# Power.net
KiCad netlist of a schematic drawn in Altium Designer
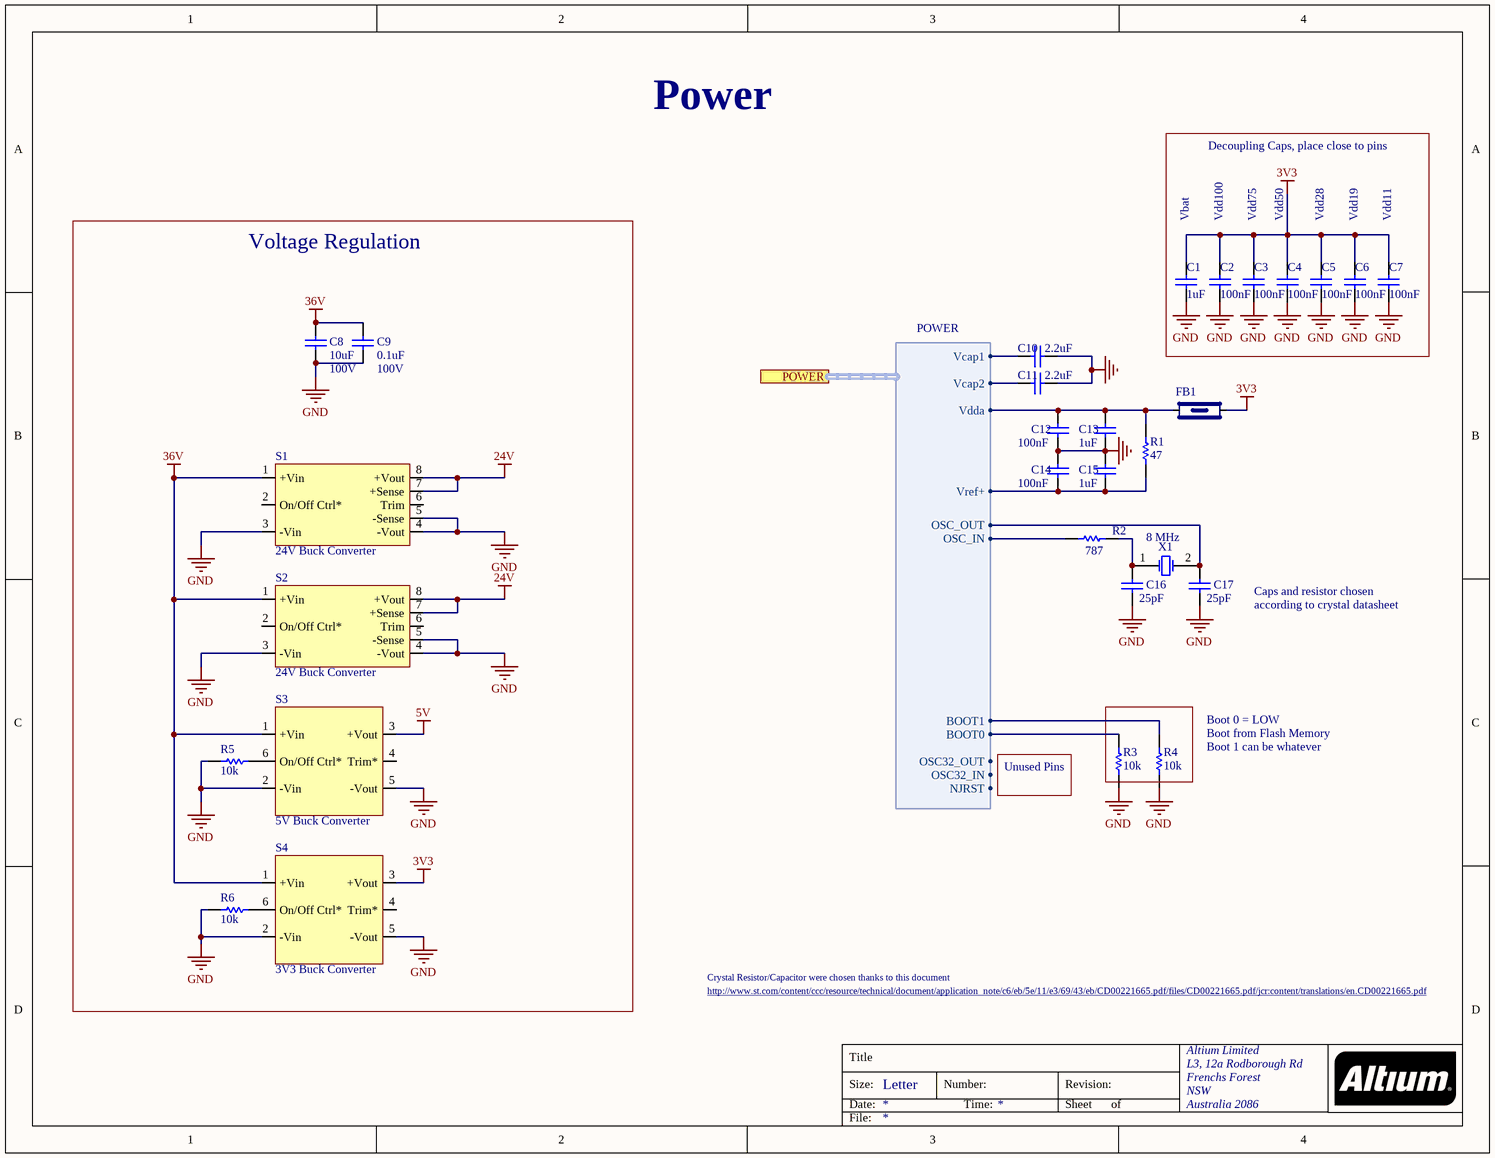
[diagram p0: Power.SchDoc]

(export (version "E")
  (design (tool "Eeschema 10.0.6"))
  (components
    (comp (ref "C1")
      (value "1uF")
      (footprint "CAP_0603")
      (description "Capacitor")
      (libsource (lib "Miscellaneous Devices") (part "Cap"))
    )
    (comp (ref "C2")
      (value "100nF")
      (footprint "CAP_0603")
      (description "Capacitor")
      (libsource (lib "Miscellaneous Devices") (part "Cap"))
    )
    (comp (ref "C3")
      (value "100nF")
      (footprint "CAP_0603")
      (description "Capacitor")
      (libsource (lib "Miscellaneous Devices") (part "Cap"))
    )
    (comp (ref "C4")
      (value "100nF")
      (footprint "CAP_0603")
      (description "Capacitor")
      (libsource (lib "Miscellaneous Devices") (part "Cap"))
    )
    (comp (ref "C5")
      (value "100nF")
      (footprint "CAP_0603")
      (description "Capacitor")
      (libsource (lib "Miscellaneous Devices") (part "Cap"))
    )
    (comp (ref "C6")
      (value "100nF")
      (footprint "CAP_0603")
      (description "Capacitor")
      (libsource (lib "Miscellaneous Devices") (part "Cap"))
    )
    (comp (ref "C7")
      (value "100nF")
      (footprint "CAP_0603")
      (description "Capacitor")
      (libsource (lib "Miscellaneous Devices") (part "Cap"))
    )
    (comp (ref "C8")
      (value "10uF")
      (footprint "2220")
      (description "Capacitor")
      (fields
        (field (name "VOLTAGE") "100V")
        (field (name "Comment") "Cap")
        (field (name "PUBLISHER") "Altium Limited")
      )
      (libsource (lib "Miscellaneous Devices") (part "Cap"))
    )
    (comp (ref "C9")
      (value "0.1uF")
      (footprint "CAP_0603")
      (description "Capacitor")
      (fields
        (field (name "VOLTAGE") "100V")
        (field (name "Comment") "Cap")
        (field (name "PUBLISHER") "Altium Limited")
      )
      (libsource (lib "Miscellaneous Devices") (part "Cap"))
    )
    (comp (ref "C10")
      (value "2.2uF")
      (footprint "CAP_0603")
      (description "Capacitor")
      (libsource (lib "Miscellaneous Devices") (part "Cap"))
    )
    (comp (ref "C11")
      (value "2.2uF")
      (footprint "CAP_0603")
      (description "Capacitor")
      (libsource (lib "Miscellaneous Devices") (part "Cap"))
    )
    (comp (ref "C12")
      (value "100nF")
      (footprint "CAP_0603")
      (description "Capacitor")
      (libsource (lib "Miscellaneous Devices") (part "Cap"))
    )
    (comp (ref "C13")
      (value "1uF")
      (footprint "CAP_0603")
      (description "Capacitor")
      (libsource (lib "Miscellaneous Devices") (part "Cap"))
    )
    (comp (ref "C14")
      (value "100nF")
      (footprint "CAP_0603")
      (description "Capacitor")
      (libsource (lib "Miscellaneous Devices") (part "Cap"))
    )
    (comp (ref "C15")
      (value "1uF")
      (footprint "CAP_0603")
      (description "Capacitor")
      (libsource (lib "Miscellaneous Devices") (part "Cap"))
    )
    (comp (ref "C16")
      (value "25pF")
      (footprint "CAP_0603")
      (description "Capacitor")
      (libsource (lib "Miscellaneous Devices") (part "Cap"))
    )
    (comp (ref "C17")
      (value "25pF")
      (footprint "CAP_0603")
      (description "Capacitor")
      (libsource (lib "Miscellaneous Devices") (part "Cap"))
    )
    (comp (ref "FB1")
      (value "Ferrite Bead")
      (footprint "0603")
      (libsource (lib "LaunchyRIOComponents") (part "Ferrite Bead"))
    )
    (comp (ref "R1")
      (value "47")
      (footprint "RES_0603")
      (description "Resistor")
      (fields (field (name "Comment") "Res1"))
      (libsource (lib "Miscellaneous Devices") (part "Res1"))
    )
    (comp (ref "R2")
      (value "787")
      (footprint "RES_0603")
      (description "Resistor")
      (fields (field (name "Comment") "Res1"))
      (libsource (lib "Miscellaneous Devices") (part "Res1"))
    )
    (comp (ref "R3")
      (value "10k")
      (footprint "RES_0603")
      (description "Resistor")
      (fields (field (name "Comment") "Res1"))
      (libsource (lib "Miscellaneous Devices") (part "Res1"))
    )
    (comp (ref "R4")
      (value "10k")
      (footprint "RES_0603")
      (description "Resistor")
      (fields (field (name "Comment") "Res1"))
      (libsource (lib "Miscellaneous Devices") (part "Res1"))
    )
    (comp (ref "R5")
      (value "10k")
      (footprint "RES_0603")
      (description "Resistor")
      (fields (field (name "Comment") "Res1"))
      (libsource (lib "Miscellaneous Devices") (part "Res1"))
    )
    (comp (ref "R6")
      (value "10k")
      (footprint "RES_0603")
      (description "Resistor")
      (fields (field (name "Comment") "Res1"))
      (libsource (lib "Miscellaneous Devices") (part "Res1"))
    )
    (comp (ref "S1")
      (value "24V Buck Converter")
      (footprint "UWE-24/3-Q12")
      (description "CONV DC/DC 72W 24V 3A")
      (libsource (lib "LaunchyRIOComponents") (part "UWE-24/3-Q12PB-C"))
    )
    (comp (ref "S2")
      (value "24V Buck Converter")
      (footprint "UWE-24/3-Q12")
      (description "CONV DC/DC 72W 24V 3A")
      (libsource (lib "LaunchyRIOComponents") (part "UWE-24/3-Q12PB-C"))
    )
    (comp (ref "S3")
      (value "5V Buck Converter")
      (footprint "SPM15-050-Q12P-C")
      (description "DC/DC CONVERTER 5V 15W")
      (libsource (lib "LaunchyRIOComponents") (part "SPM15-050-Q12P-C"))
    )
    (comp (ref "S4")
      (value "3V3 Buck Converter")
      (footprint "SPM15-033-Q48N-C")
      (description "DC/DC CONVERTER 3.3V 15W")
      (libsource (lib "LaunchyRIOComponents") (part "SPM15-033-Q12P-C"))
    )
    (comp (ref "X1")
      (value "XTAL")
      (footprint "OSC_8MHz")
      (description "Crystal Oscillator")
      (fields (field (name "FREQUENCY") "8 MHz"))
      (libsource (lib "Miscellaneous Devices") (part "XTAL"))
    )
  )
  (nets
    (net (code "2") (name "/BOOT0") (class "Default")
      (node (ref "R3") (pin "2") (pinfunction "2_2") (pintype "passive"))
    )
    (net (code "3") (name "/BOOT1") (class "Default")
      (node (ref "R4") (pin "2") (pinfunction "2_2") (pintype "passive"))
    )
    (net (code "4") (name "/OSC_IN") (class "Default")
      (node (ref "R2") (pin "2") (pinfunction "2_2") (pintype "passive"))
    )
    (net (code "5") (name "/OSC_OUT") (class "Default")
      (node (ref "C17") (pin "2") (pinfunction "2_2") (pintype "passive"))
      (node (ref "X1") (pin "2") (pinfunction "OSC2_2") (pintype "passive"))
    )
    (net (code "6") (name "/Vcap1") (class "Default")
      (node (ref "C10") (pin "2") (pinfunction "2_2") (pintype "passive"))
    )
    (net (code "7") (name "/Vcap2") (class "Default")
      (node (ref "C11") (pin "2") (pinfunction "2_2") (pintype "passive"))
    )
    (net (code "8") (name "/Vdda") (class "Default")
      (node (ref "C12") (pin "2") (pinfunction "2_2") (pintype "passive"))
      (node (ref "C13") (pin "2") (pinfunction "2_2") (pintype "passive"))
      (node (ref "FB1") (pin "1") (pinfunction "1_1") (pintype "passive"))
      (node (ref "R1") (pin "2") (pinfunction "2_2") (pintype "passive"))
    )
    (net (code "9") (name "/Vref+") (class "Default")
      (node (ref "C14") (pin "1") (pinfunction "1_1") (pintype "passive"))
      (node (ref "C15") (pin "1") (pinfunction "1_1") (pintype "passive"))
      (node (ref "R1") (pin "1") (pinfunction "1_1") (pintype "passive"))
    )
    (net (code "11") (name "3V3") (class "Default")
      (node (ref "C1") (pin "2") (pinfunction "2_2") (pintype "passive"))
      (node (ref "C2") (pin "2") (pinfunction "2_2") (pintype "passive"))
      (node (ref "C3") (pin "2") (pinfunction "2_2") (pintype "passive"))
      (node (ref "C4") (pin "2") (pinfunction "2_2") (pintype "passive"))
      (node (ref "C5") (pin "2") (pinfunction "2_2") (pintype "passive"))
      (node (ref "C6") (pin "2") (pinfunction "2_2") (pintype "passive"))
      (node (ref "C7") (pin "2") (pinfunction "2_2") (pintype "passive"))
      (node (ref "FB1") (pin "2") (pinfunction "2_2") (pintype "passive"))
      (node (ref "S4") (pin "3") (pinfunction "+Vout_3") (pintype "passive"))
    )
    (net (code "12") (name "5V") (class "Default")
      (node (ref "S3") (pin "3") (pinfunction "+Vout_3") (pintype "passive"))
    )
    (net (code "13") (name "24V") (class "Default")
      (node (ref "S1") (pin "7") (pinfunction "+Sense_7") (pintype "passive"))
      (node (ref "S1") (pin "8") (pinfunction "+Vout_8") (pintype "passive"))
      (node (ref "S2") (pin "7") (pinfunction "+Sense_7") (pintype "passive"))
      (node (ref "S2") (pin "8") (pinfunction "+Vout_8") (pintype "passive"))
    )
    (net (code "14") (name "36V") (class "Default")
      (node (ref "C8") (pin "2") (pinfunction "2_2") (pintype "passive"))
      (node (ref "C9") (pin "2") (pinfunction "2_2") (pintype "passive"))
      (node (ref "S1") (pin "1") (pinfunction "+Vin_1") (pintype "passive"))
      (node (ref "S2") (pin "1") (pinfunction "+Vin_1") (pintype "passive"))
      (node (ref "S3") (pin "1") (pinfunction "+Vin_1") (pintype "passive"))
      (node (ref "S4") (pin "1") (pinfunction "+Vin_1") (pintype "passive"))
    )
    (net (code "15") (name "GND") (class "Default")
      (node (ref "C1") (pin "1") (pinfunction "1_1") (pintype "passive"))
      (node (ref "C10") (pin "1") (pinfunction "1_1") (pintype "passive"))
      (node (ref "C11") (pin "1") (pinfunction "1_1") (pintype "passive"))
      (node (ref "C12") (pin "1") (pinfunction "1_1") (pintype "passive"))
      (node (ref "C13") (pin "1") (pinfunction "1_1") (pintype "passive"))
      (node (ref "C14") (pin "2") (pinfunction "2_2") (pintype "passive"))
      (node (ref "C15") (pin "2") (pinfunction "2_2") (pintype "passive"))
      (node (ref "C16") (pin "1") (pinfunction "1_1") (pintype "passive"))
      (node (ref "C17") (pin "1") (pinfunction "1_1") (pintype "passive"))
      (node (ref "C2") (pin "1") (pinfunction "1_1") (pintype "passive"))
      (node (ref "C3") (pin "1") (pinfunction "1_1") (pintype "passive"))
      (node (ref "C4") (pin "1") (pinfunction "1_1") (pintype "passive"))
      (node (ref "C5") (pin "1") (pinfunction "1_1") (pintype "passive"))
      (node (ref "C6") (pin "1") (pinfunction "1_1") (pintype "passive"))
      (node (ref "C7") (pin "1") (pinfunction "1_1") (pintype "passive"))
      (node (ref "C8") (pin "1") (pinfunction "1_1") (pintype "passive"))
      (node (ref "C9") (pin "1") (pinfunction "1_1") (pintype "passive"))
      (node (ref "R3") (pin "1") (pinfunction "1_1") (pintype "passive"))
      (node (ref "R4") (pin "1") (pinfunction "1_1") (pintype "passive"))
      (node (ref "R5") (pin "2") (pinfunction "2_2") (pintype "passive"))
      (node (ref "R6") (pin "2") (pinfunction "2_2") (pintype "passive"))
      (node (ref "S1") (pin "3") (pinfunction "-Vin_3") (pintype "passive"))
      (node (ref "S1") (pin "4") (pinfunction "-Vout_4") (pintype "passive"))
      (node (ref "S1") (pin "5") (pinfunction "-Sense_5") (pintype "passive"))
      (node (ref "S2") (pin "3") (pinfunction "-Vin_3") (pintype "passive"))
      (node (ref "S2") (pin "4") (pinfunction "-Vout_4") (pintype "passive"))
      (node (ref "S2") (pin "5") (pinfunction "-Sense_5") (pintype "passive"))
      (node (ref "S3") (pin "2") (pinfunction "-Vin_2") (pintype "passive"))
      (node (ref "S3") (pin "5") (pinfunction "-Vout_5") (pintype "passive"))
      (node (ref "S4") (pin "2") (pinfunction "-Vin_2") (pintype "passive"))
      (node (ref "S4") (pin "5") (pinfunction "-Vout_5") (pintype "passive"))
    )
    (net (code "16") (name "Net-(S3-On{slash}Off_Ctrl*)") (class "Default")
      (node (ref "R5") (pin "1") (pinfunction "1_1") (pintype "passive"))
      (node (ref "S3") (pin "6") (pinfunction "On/Off_Ctrl*_6") (pintype "passive"))
    )
    (net (code "17") (name "Net-(S4-On{slash}Off_Ctrl*)") (class "Default")
      (node (ref "R6") (pin "1") (pinfunction "1_1") (pintype "passive"))
      (node (ref "S4") (pin "6") (pinfunction "On/Off_Ctrl*_6") (pintype "passive"))
    )
    (net (code "18") (name "Net-(X1-OSC1)") (class "Default")
      (node (ref "C16") (pin "2") (pinfunction "2_2") (pintype "passive"))
      (node (ref "R2") (pin "1") (pinfunction "1_1") (pintype "passive"))
      (node (ref "X1") (pin "1") (pinfunction "OSC1_1") (pintype "passive"))
    )
    (net (code "19") (name "unconnected-(S1-On{slash}Off_Ctrl*-Pad2)") (class "Default")
      (node (ref "S1") (pin "2") (pinfunction "On/Off_Ctrl*_2") (pintype "passive"))
    )
    (net (code "20") (name "unconnected-(S1-Trim-Pad6)") (class "Default")
      (node (ref "S1") (pin "6") (pinfunction "Trim_6") (pintype "passive"))
    )
    (net (code "21") (name "unconnected-(S2-On{slash}Off_Ctrl*-Pad2)") (class "Default")
      (node (ref "S2") (pin "2") (pinfunction "On/Off_Ctrl*_2") (pintype "passive"))
    )
    (net (code "22") (name "unconnected-(S2-Trim-Pad6)") (class "Default")
      (node (ref "S2") (pin "6") (pinfunction "Trim_6") (pintype "passive"))
    )
    (net (code "23") (name "unconnected-(S3-Trim*-Pad4)") (class "Default")
      (node (ref "S3") (pin "4") (pinfunction "Trim*_4") (pintype "passive"))
    )
    (net (code "24") (name "unconnected-(S4-Trim*-Pad4)") (class "Default")
      (node (ref "S4") (pin "4") (pinfunction "Trim*_4") (pintype "passive"))
    )
  )
)
